# Lipo_Saver_Buzzer_only.net
KiCad netlist of a schematic drawn in Altium Designer
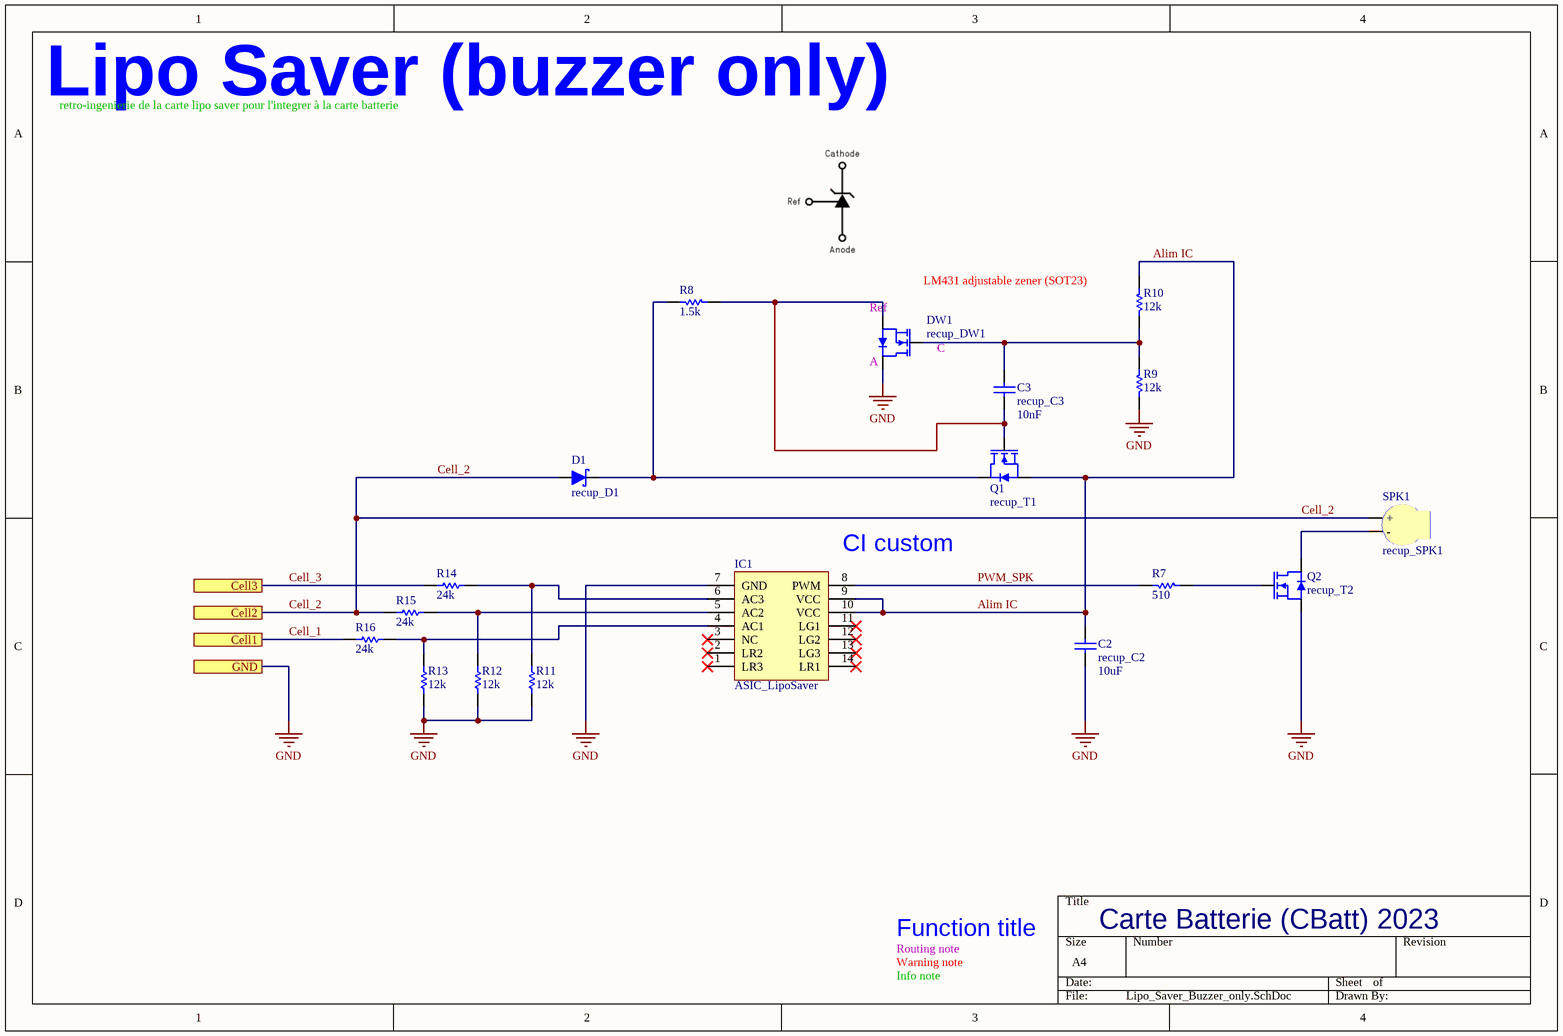
[diagram p0: Lipo_Saver_Buzzer_only.SchDoc]

(export (version "E")
  (design (tool "Eeschema 10.0.6"))
  (components
    (comp (ref "C2")
      (value "recup_C2")
      (footprint "WCAP-CSGP_0805, 2x1.25x1.25")
      (description "CAP CER 1uF 50V X7R 0805")
      (fields
        (field (name "MANUFACTURER") "Wurth Elektronik")
        (field (name "MANUFACTURER PART NUMBER") "885012207103")
        (field (name "ALTIUM_VALUE") "10uF")
      )
      (libsource (lib "Condensateur") (part "WCAP-CSGP, 885012207103"))
    )
    (comp (ref "C3")
      (value "recup_C3")
      (footprint "WCAP-CSGP_0603, 1.6x0.8x0.8")
      (description "CAP CER 100nF 50V X7R 0603")
      (fields
        (field (name "ALTIUM_VALUE") "10nF")
        (field (name "MANUFACTURER") "Wurth Elektronik")
        (field (name "MANUFACTURER PART NUMBER") "885012206095")
      )
      (libsource (lib "Condensateur") (part "WCAP-CSGP, 885012206095"))
    )
    (comp (ref "D1")
      (value "recup_D1")
      (footprint "SOD-123FL")
      (description "DIODE SCHOTTKY 40V 3A SOD123-FL")
      (fields (field (name "MANUFACTURER") "ROHM") (field (name "MANUFACTURER PART NUMBER") "RBR3MM40ATFTR"))
      (libsource (lib "Diode") (part "RBR3MM40ATFTR"))
    )
    (comp (ref "DW1")
      (value "recup_DW1")
      (footprint "SOT-23")
      (description "MOSFET N 60V 115MA SOT23")
      (fields
        (field (name "MANUFACTURER") "Changjiang Electronics Tech (CJ)")
        (field (name "MANUFACTURER PART NUMBER") "2N7002")
      )
      (libsource (lib "Transistors") (part "2N7002"))
    )
    (comp (ref "IC1")
      (value "ASIC_LipoSaver")
      (footprint "SOIC127P600X175-14N")
      (description "Specific IC for Lipo Saver (extracted")
      (fields (field (name "MANUFACTURER") "LipoSaver"))
      (libsource (lib "CI") (part "ASIC_LipoSaver"))
    )
    (comp (ref "Q1")
      (value "recup_T1")
      (footprint "SOT-23")
      (description "MOSFET N 60V 115MA SOT23")
      (fields
        (field (name "MANUFACTURER") "Changjiang Electronics Tech (CJ)")
        (field (name "MANUFACTURER PART NUMBER") "2N7002")
      )
      (libsource (lib "Transistors") (part "2N7002"))
    )
    (comp (ref "Q2")
      (value "recup_T2")
      (footprint "SOT-23")
      (description "MOSFET N 60V 115MA SOT23")
      (fields
        (field (name "MANUFACTURER") "Changjiang Electronics Tech (CJ)")
        (field (name "MANUFACTURER PART NUMBER") "2N7002")
      )
      (libsource (lib "Transistors") (part "2N7002"))
    )
    (comp (ref "R7")
      (value "510")
      (footprint "RESC1608X06N")
      (description "RES SMD 100K OHM 1% 1/10W 0603")
      (fields
        (field (name "MANUFACTURER") "Yageo")
        (field (name "MANUFACTURER PART NUMBER") "RC0603FR-07100KL")
      )
      (libsource (lib "Resistance") (part "RC0603FR-07100KL"))
    )
    (comp (ref "R8")
      (value "1.5k")
      (footprint "RESC1608X06N")
      (description "RES SMD 100K OHM 1% 1/10W 0603")
      (fields
        (field (name "MANUFACTURER") "Yageo")
        (field (name "MANUFACTURER PART NUMBER") "RC0603FR-07100KL")
      )
      (libsource (lib "Resistance") (part "RC0603FR-07100KL"))
    )
    (comp (ref "R9")
      (value "12k")
      (footprint "RESC1608X06N")
      (description "RES SMD 100K OHM 1% 1/10W 0603")
      (fields
        (field (name "MANUFACTURER") "Yageo")
        (field (name "MANUFACTURER PART NUMBER") "RC0603FR-07100KL")
      )
      (libsource (lib "Resistance") (part "RC0603FR-07100KL"))
    )
    (comp (ref "R10")
      (value "12k")
      (footprint "RESC1608X06N")
      (description "RES SMD 100K OHM 1% 1/10W 0603")
      (fields
        (field (name "MANUFACTURER") "Yageo")
        (field (name "MANUFACTURER PART NUMBER") "RC0603FR-07100KL")
      )
      (libsource (lib "Resistance") (part "RC0603FR-07100KL"))
    )
    (comp (ref "R11")
      (value "12k")
      (footprint "RESC1608X06N")
      (description "RES SMD 100K OHM 1% 1/10W 0603")
      (fields
        (field (name "MANUFACTURER") "Yageo")
        (field (name "MANUFACTURER PART NUMBER") "RC0603FR-07100KL")
      )
      (libsource (lib "Resistance") (part "RC0603FR-07100KL"))
    )
    (comp (ref "R12")
      (value "12k")
      (footprint "RESC1608X06N")
      (description "RES SMD 100K OHM 1% 1/10W 0603")
      (fields
        (field (name "MANUFACTURER") "Yageo")
        (field (name "MANUFACTURER PART NUMBER") "RC0603FR-07100KL")
      )
      (libsource (lib "Resistance") (part "RC0603FR-07100KL"))
    )
    (comp (ref "R13")
      (value "12k")
      (footprint "RESC1608X06N")
      (description "RES SMD 100K OHM 1% 1/10W 0603")
      (fields
        (field (name "MANUFACTURER") "Yageo")
        (field (name "MANUFACTURER PART NUMBER") "RC0603FR-07100KL")
      )
      (libsource (lib "Resistance") (part "RC0603FR-07100KL"))
    )
    (comp (ref "R14")
      (value "24k")
      (footprint "RESC1608X06N")
      (description "RES SMD 100K OHM 1% 1/10W 0603")
      (fields
        (field (name "MANUFACTURER") "Yageo")
        (field (name "MANUFACTURER PART NUMBER") "RC0603FR-07100KL")
      )
      (libsource (lib "Resistance") (part "RC0603FR-07100KL"))
    )
    (comp (ref "R15")
      (value "24k")
      (footprint "RESC1608X06N")
      (description "RES SMD 100K OHM 1% 1/10W 0603")
      (fields
        (field (name "MANUFACTURER") "Yageo")
        (field (name "MANUFACTURER PART NUMBER") "RC0603FR-07100KL")
      )
      (libsource (lib "Resistance") (part "RC0603FR-07100KL"))
    )
    (comp (ref "R16")
      (value "24k")
      (footprint "RESC1608X06N")
      (description "RES SMD 100K OHM 1% 1/10W 0603")
      (fields
        (field (name "MANUFACTURER") "Yageo")
        (field (name "MANUFACTURER PART NUMBER") "RC0603FR-07100KL")
      )
      (libsource (lib "Resistance") (part "RC0603FR-07100KL"))
    )
    (comp (ref "SPK1")
      (value "recup_SPK1")
      (footprint "BUZZER_LipoSaver")
      (description "Cavalier soudure \"ouvert\" + empreinte dipole 0603")
      (libsource (lib "Divers") (part "BUZZER_LipoSaver"))
    )
  )
  (nets
    (net (code "1") (name "/Alim IC") (class "Default")
      (node (ref "C2") (pin "2") (pinfunction "2_2") (pintype "passive"))
      (node (ref "IC1") (pin "10") (pinfunction "VCC_10") (pintype "passive"))
      (node (ref "IC1") (pin "9") (pinfunction "VCC_9") (pintype "passive"))
      (node (ref "Q1") (pin "2") (pinfunction "S_2") (pintype "passive"))
      (node (ref "R10") (pin "2") (pinfunction "2_2") (pintype "passive"))
    )
    (net (code "2") (name "/Cell_1") (class "Default")
      (node (ref "R16") (pin "2") (pinfunction "2_2") (pintype "passive"))
    )
    (net (code "3") (name "/Cell_2") (class "Default")
      (node (ref "D1") (pin "1") (pintype "passive"))
      (node (ref "R15") (pin "2") (pinfunction "2_2") (pintype "passive"))
      (node (ref "SPK1") (pin "1") (pinfunction "+_1") (pintype "passive"))
    )
    (net (code "4") (name "/Cell_3") (class "Default")
      (node (ref "R14") (pin "2") (pinfunction "2_2") (pintype "passive"))
    )
    (net (code "5") (name "/PWM_SPK") (class "Default")
      (node (ref "IC1") (pin "8") (pinfunction "PWM_8") (pintype "passive"))
      (node (ref "R7") (pin "1") (pinfunction "1_1") (pintype "passive"))
    )
    (net (code "6") (name "GND") (class "Default")
      (node (ref "C2") (pin "1") (pinfunction "1_1") (pintype "passive"))
      (node (ref "DW1") (pin "3") (pinfunction "D_3") (pintype "passive"))
      (node (ref "IC1") (pin "7") (pinfunction "GND_7") (pintype "passive"))
      (node (ref "Q2") (pin "2") (pinfunction "S_2") (pintype "passive"))
      (node (ref "R11") (pin "1") (pinfunction "1_1") (pintype "passive"))
      (node (ref "R12") (pin "1") (pinfunction "1_1") (pintype "passive"))
      (node (ref "R13") (pin "1") (pinfunction "1_1") (pintype "passive"))
      (node (ref "R9") (pin "2") (pinfunction "2_2") (pintype "passive"))
    )
    (net (code "7") (name "Net-(DW1-G)") (class "Default")
      (node (ref "C3") (pin "2") (pinfunction "2_2") (pintype "passive"))
      (node (ref "DW1") (pin "1") (pinfunction "G_1") (pintype "passive"))
      (node (ref "R10") (pin "1") (pinfunction "1_1") (pintype "passive"))
      (node (ref "R9") (pin "1") (pinfunction "1_1") (pintype "passive"))
    )
    (net (code "8") (name "Net-(DW1-S)") (class "Default")
      (node (ref "C3") (pin "1") (pinfunction "1_1") (pintype "passive"))
      (node (ref "DW1") (pin "2") (pinfunction "S_2") (pintype "passive"))
      (node (ref "Q1") (pin "1") (pinfunction "G_1") (pintype "passive"))
      (node (ref "R8") (pin "2") (pinfunction "2_2") (pintype "passive"))
    )
    (net (code "9") (name "Net-(IC1-AC1)") (class "Default")
      (node (ref "IC1") (pin "4") (pinfunction "AC1_4") (pintype "passive"))
      (node (ref "R13") (pin "2") (pinfunction "2_2") (pintype "passive"))
      (node (ref "R16") (pin "1") (pinfunction "1_1") (pintype "passive"))
    )
    (net (code "10") (name "Net-(IC1-AC2)") (class "Default")
      (node (ref "IC1") (pin "5") (pinfunction "AC2_5") (pintype "passive"))
      (node (ref "R12") (pin "2") (pinfunction "2_2") (pintype "passive"))
      (node (ref "R15") (pin "1") (pinfunction "1_1") (pintype "passive"))
    )
    (net (code "11") (name "Net-(IC1-AC3)") (class "Default")
      (node (ref "IC1") (pin "6") (pinfunction "AC3_6") (pintype "passive"))
      (node (ref "R11") (pin "2") (pinfunction "2_2") (pintype "passive"))
      (node (ref "R14") (pin "1") (pinfunction "1_1") (pintype "passive"))
    )
    (net (code "12") (name "Net-(Q1-D)") (class "Default")
      (node (ref "D1") (pin "2") (pintype "passive"))
      (node (ref "Q1") (pin "3") (pinfunction "D_3") (pintype "passive"))
      (node (ref "R8") (pin "1") (pinfunction "1_1") (pintype "passive"))
    )
    (net (code "13") (name "Net-(Q2-D)") (class "Default")
      (node (ref "Q2") (pin "3") (pinfunction "D_3") (pintype "passive"))
      (node (ref "SPK1") (pin "2") (pinfunction "-_2") (pintype "passive"))
    )
    (net (code "14") (name "Net-(Q2-G)") (class "Default")
      (node (ref "Q2") (pin "1") (pinfunction "G_1") (pintype "passive"))
      (node (ref "R7") (pin "2") (pinfunction "2_2") (pintype "passive"))
    )
    (net (code "15") (name "unconnected-(IC1-LG1-Pad11)") (class "Default")
      (node (ref "IC1") (pin "11") (pinfunction "LG1_11") (pintype "passive+no_connect"))
    )
    (net (code "16") (name "unconnected-(IC1-LG2-Pad12)") (class "Default")
      (node (ref "IC1") (pin "12") (pinfunction "LG2_12") (pintype "passive+no_connect"))
    )
    (net (code "17") (name "unconnected-(IC1-LG3-Pad13)") (class "Default")
      (node (ref "IC1") (pin "13") (pinfunction "LG3_13") (pintype "passive+no_connect"))
    )
    (net (code "18") (name "unconnected-(IC1-LR1-Pad14)") (class "Default")
      (node (ref "IC1") (pin "14") (pinfunction "LR1_14") (pintype "passive+no_connect"))
    )
    (net (code "19") (name "unconnected-(IC1-LR2-Pad2)") (class "Default")
      (node (ref "IC1") (pin "2") (pinfunction "LR2_2") (pintype "passive+no_connect"))
    )
    (net (code "20") (name "unconnected-(IC1-LR3-Pad1)") (class "Default")
      (node (ref "IC1") (pin "1") (pinfunction "LR3_1") (pintype "passive+no_connect"))
    )
    (net (code "21") (name "unconnected-(IC1-NC-Pad3)") (class "Default")
      (node (ref "IC1") (pin "3") (pinfunction "NC_3") (pintype "passive+no_connect"))
    )
  )
)
